# Fri3D_2024_ESP32.net
KiCad netlist of a schematic drawn in Altium Designer
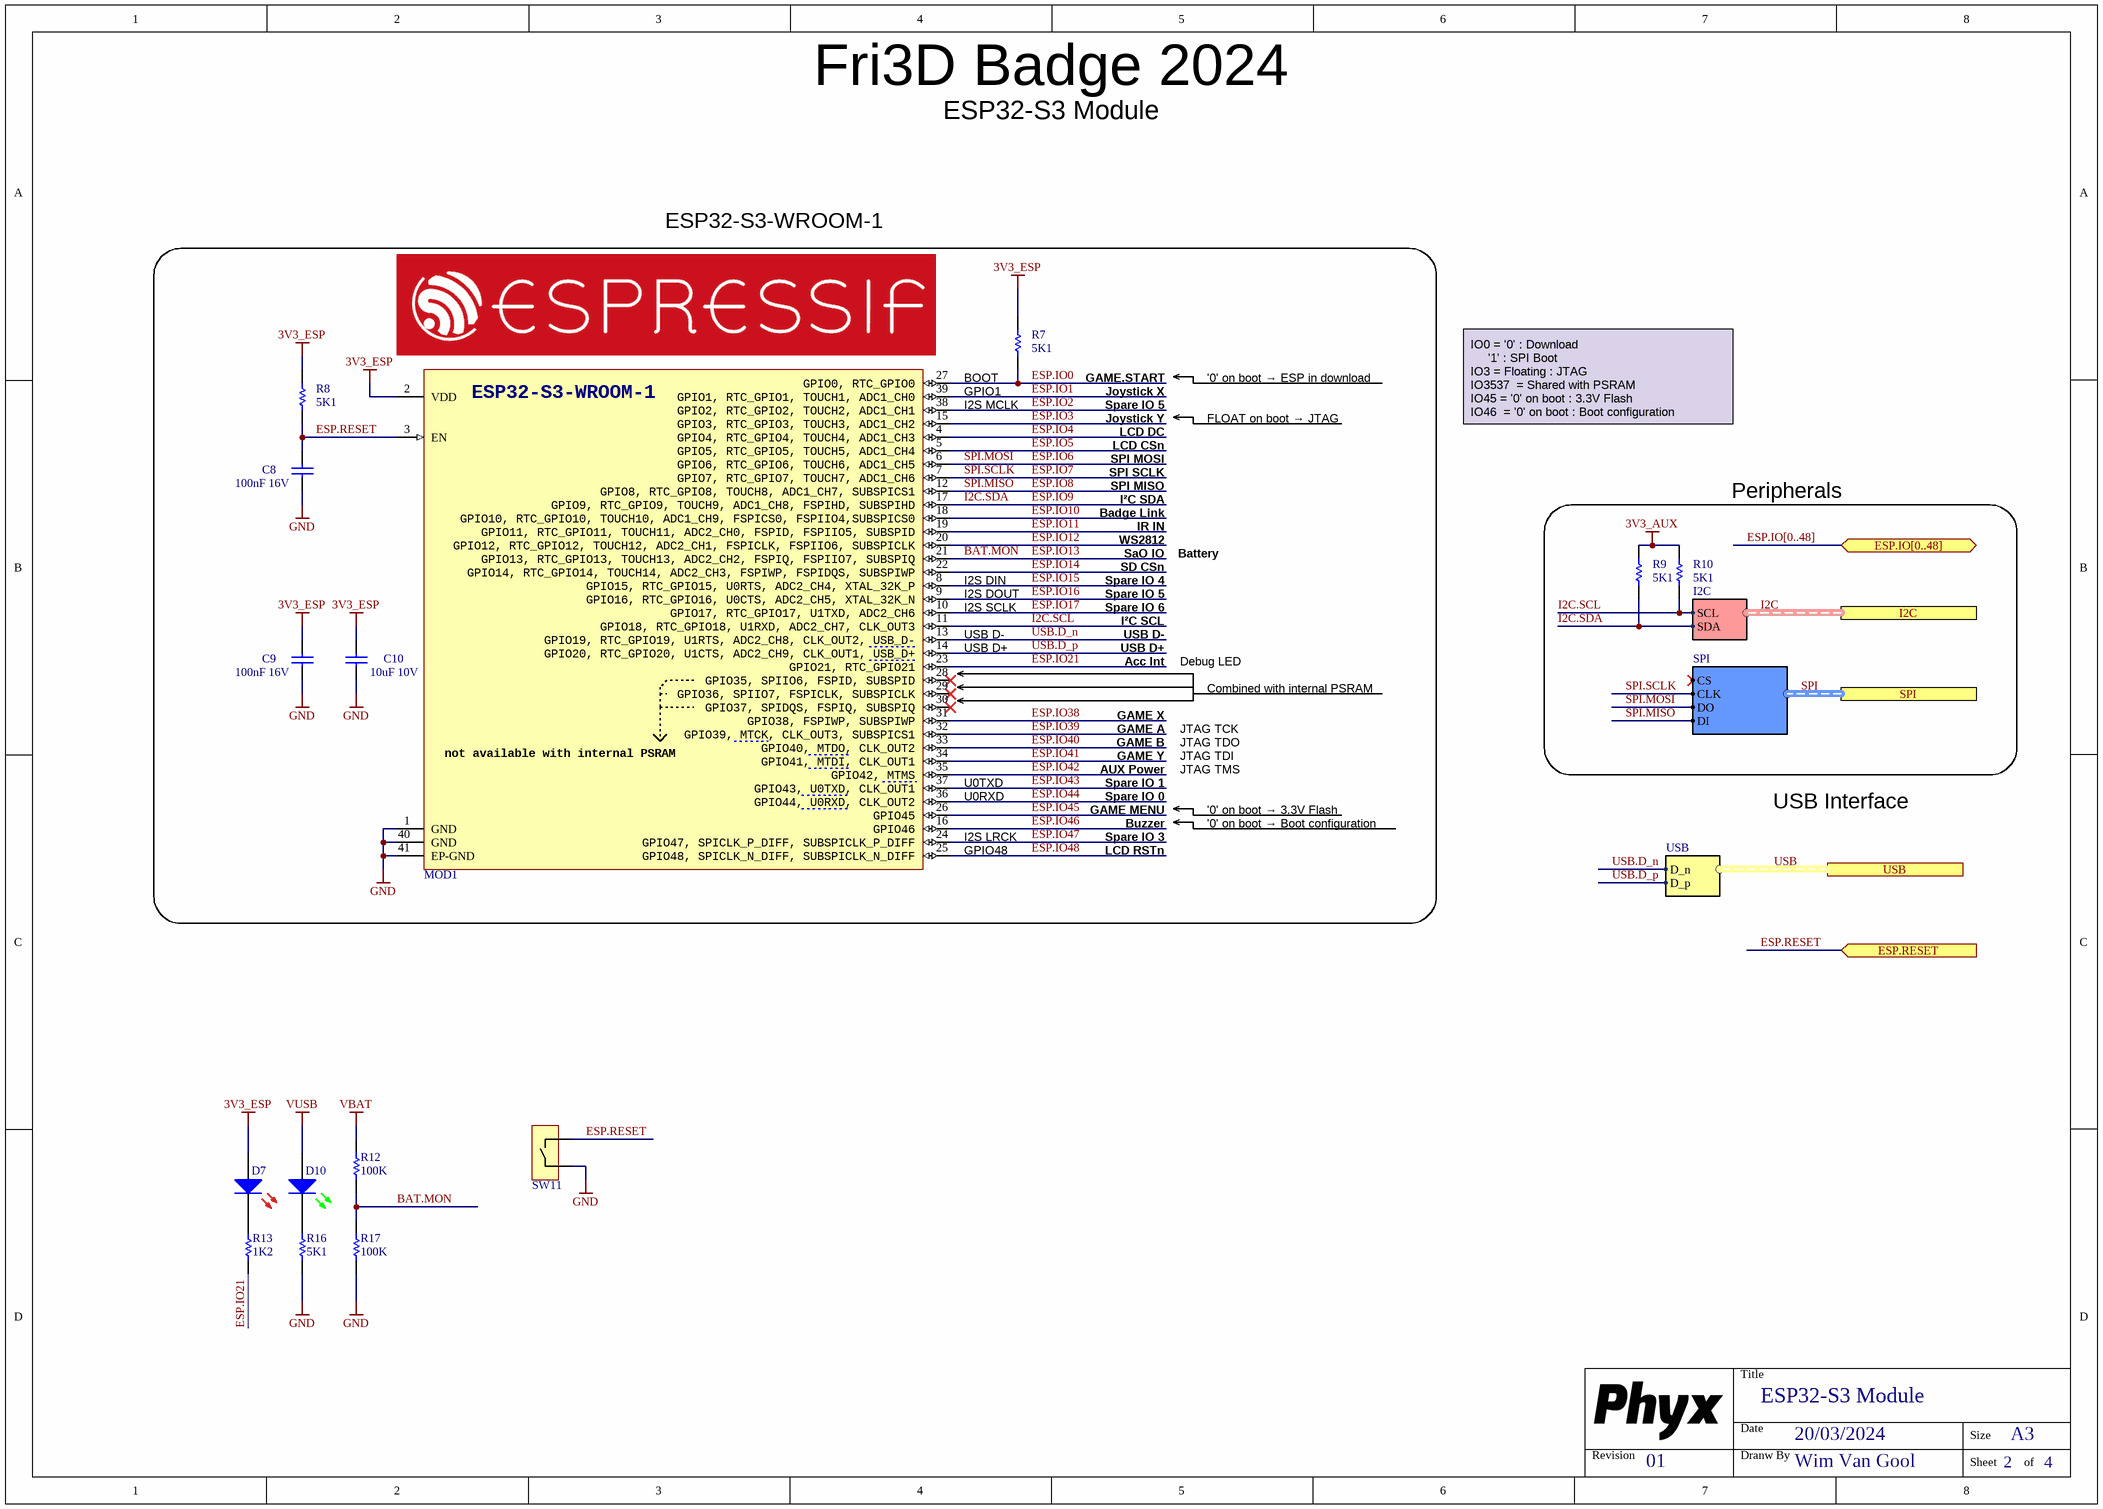
[diagram p0: Fri3D_2024_ESP32.SchDoc]

(export (version "E")
  (design (tool "Eeschema 10.0.6"))
  (components
    (comp (ref "C8")
      (value "100nF 16V")
      (footprint "C0603_N")
      (description "Capacitor Ceramic")
      (libsource (lib "Phyx_Components") (part "CAP_CERAMIC"))
    )
    (comp (ref "C9")
      (value "100nF 16V")
      (footprint "C0603_N")
      (description "Capacitor Ceramic")
      (libsource (lib "Phyx_Components") (part "CAP_CERAMIC"))
    )
    (comp (ref "C10")
      (value "10uF 10V")
      (footprint "C0805_N")
      (description "Capacitor Ceramic")
      (fields (field (name "Comment") "CAP_CERAMIC"))
      (libsource (lib "Phyx_Components") (part "CAP_CERAMIC"))
    )
    (comp (ref "D7")
      (value "Default 0805 Red LED")
      (footprint "LED_0805_RD")
      (description "=Description")
      (libsource (lib "Phyx_Components") (part "LED_RED"))
    )
    (comp (ref "D10")
      (value "Default 0805 Green LED")
      (footprint "LED_0805_GR")
      (description "=Description")
      (libsource (lib "Phyx_Components") (part "LED_GREEN"))
    )
    (comp (ref "MOD1")
      (value "ESP32-S3 based WROOM-1 16MB Flash, 8MB PSRAM")
      (footprint "ESP-ESP32-S3-WROOM-1")
      (description "WiFi # MOD ESP32-S3-WROOM-1")
      (libsource (lib "Phyx_Components") (part "ESP-ESP32-S3-WROOM-1"))
    )
    (comp (ref "R7")
      (value "5K1")
      (footprint "R0603_N")
      (fields (field (name "Comment") "RESISTOR"))
      (libsource (lib "Phyx_Components") (part "RESISTOR"))
    )
    (comp (ref "R8")
      (value "5K1")
      (footprint "R0603_N")
      (fields (field (name "Comment") "RESISTOR"))
      (libsource (lib "Phyx_Components") (part "RESISTOR"))
    )
    (comp (ref "R9")
      (value "5K1")
      (footprint "R0603_N")
      (fields (field (name "Comment") "RESISTOR"))
      (libsource (lib "Phyx_Components") (part "RESISTOR"))
    )
    (comp (ref "R10")
      (value "5K1")
      (footprint "R0603_N")
      (fields (field (name "Comment") "RESISTOR"))
      (libsource (lib "Phyx_Components") (part "RESISTOR"))
    )
    (comp (ref "R12")
      (value "100K")
      (footprint "R0603_N")
      (fields (field (name "Comment") "RESISTOR"))
      (libsource (lib "Phyx_Components") (part "RESISTOR"))
    )
    (comp (ref "R13")
      (value "1K2")
      (footprint "R0603_N")
      (fields (field (name "Comment") "RESISTOR"))
      (libsource (lib "Phyx_Components") (part "RESISTOR"))
    )
    (comp (ref "R16")
      (value "5K1")
      (footprint "R0603_N")
      (fields (field (name "Comment") "RESISTOR"))
      (libsource (lib "Phyx_Components") (part "RESISTOR"))
    )
    (comp (ref "R17")
      (value "100K")
      (footprint "R0603_N")
      (fields (field (name "Comment") "RESISTOR"))
      (libsource (lib "Phyx_Components") (part "RESISTOR"))
    )
    (comp (ref "SW11")
      (value "SKPMAME010 6x6 TACTG Switch")
      (footprint "ALPS_SKPMAME010")
      (libsource (lib "Phyx_Components") (part "SW_TACT"))
    )
  )
  (nets
    (net (code "23") (name "/ESP.IO0") (class "Default")
      (node (ref "MOD1") (pin "27") (pinfunction "GPIO0,_RTC_GPIO0_27") (pintype "bidirectional"))
      (node (ref "R7") (pin "2") (pinfunction "2_2") (pintype "passive"))
    )
    (net (code "24") (name "/ESP.IO1") (class "Default")
      (node (ref "MOD1") (pin "39") (pinfunction "GPIO1,_RTC_GPIO1,_TOUCH1,_ADC1_CH0_39") (pintype "bidirectional"))
    )
    (net (code "25") (name "/ESP.IO2") (class "Default")
      (node (ref "MOD1") (pin "38") (pinfunction "GPIO2,_RTC_GPIO2,_TOUCH2,_ADC1_CH1_38") (pintype "bidirectional"))
    )
    (net (code "26") (name "/ESP.IO3") (class "Default")
      (node (ref "MOD1") (pin "15") (pinfunction "GPIO3,_RTC_GPIO3,_TOUCH3,_ADC1_CH2_15") (pintype "bidirectional"))
    )
    (net (code "27") (name "/ESP.IO4") (class "Default")
      (node (ref "MOD1") (pin "4") (pinfunction "GPIO4,_RTC_GPIO4,_TOUCH4,_ADC1_CH3_4") (pintype "bidirectional"))
    )
    (net (code "28") (name "/ESP.IO5") (class "Default")
      (node (ref "MOD1") (pin "5") (pinfunction "GPIO5,_RTC_GPIO5,_TOUCH5,_ADC1_CH4_5") (pintype "bidirectional"))
    )
    (net (code "29") (name "/ESP.IO6") (class "Default")
      (node (ref "MOD1") (pin "6") (pinfunction "GPIO6,_RTC_GPIO6,_TOUCH6,_ADC1_CH5_6") (pintype "bidirectional"))
    )
    (net (code "30") (name "/ESP.IO7") (class "Default")
      (node (ref "MOD1") (pin "7") (pinfunction "GPIO7,_RTC_GPIO7,_TOUCH7,_ADC1_CH6_7") (pintype "bidirectional"))
    )
    (net (code "31") (name "/ESP.IO8") (class "Default")
      (node (ref "MOD1") (pin "12") (pinfunction "GPIO8,_RTC_GPIO8,_TOUCH8,_ADC1_CH7,_SUBSPICS1_12") (pintype "bidirectional"))
    )
    (net (code "32") (name "/ESP.IO9") (class "Default")
      (node (ref "MOD1") (pin "17") (pinfunction "GPIO9,_RTC_GPIO9,_TOUCH9,_ADC1_CH8,_FSPIHD,_SUBSPIHD_17") (pintype "bidirectional"))
      (node (ref "R9") (pin "2") (pinfunction "2_2") (pintype "passive"))
    )
    (net (code "33") (name "/ESP.IO10") (class "Default")
      (node (ref "MOD1") (pin "18") (pinfunction "GPIO10,_RTC_GPIO10,_TOUCH10,_ADC1_CH9,_FSPICS0,_FSPIIO4,SUBSPICS0_18") (pintype "bidirectional"))
    )
    (net (code "34") (name "/ESP.IO11") (class "Default")
      (node (ref "MOD1") (pin "19") (pinfunction "GPIO11,_RTC_GPIO11,_TOUCH11,_ADC2_CH0,_FSPID,_FSPIIO5,_SUBSPID_19") (pintype "bidirectional"))
    )
    (net (code "35") (name "/ESP.IO12") (class "Default")
      (node (ref "MOD1") (pin "20") (pinfunction "GPIO12,_RTC_GPIO12,_TOUCH12,_ADC2_CH1,_FSPICLK,_FSPIIO6,_SUBSPICLK_20") (pintype "bidirectional"))
    )
    (net (code "36") (name "/ESP.IO13") (class "Default")
      (node (ref "MOD1") (pin "21") (pinfunction "GPIO13,_RTC_GPIO13,_TOUCH13,_ADC2_CH2,_FSPIQ,_FSPIIO7,_SUBSPIQ_21") (pintype "bidirectional"))
      (node (ref "R12") (pin "2") (pinfunction "2_2") (pintype "passive"))
      (node (ref "R17") (pin "1") (pinfunction "1_1") (pintype "passive"))
    )
    (net (code "37") (name "/ESP.IO14") (class "Default")
      (node (ref "MOD1") (pin "22") (pinfunction "GPIO14,_RTC_GPIO14,_TOUCH14,_ADC2_CH3,_FSPIWP,_FSPIDQS,_SUBSPIWP_22") (pintype "bidirectional"))
    )
    (net (code "38") (name "/ESP.IO15") (class "Default")
      (node (ref "MOD1") (pin "8") (pinfunction "GPIO15,_RTC_GPIO15,_U0RTS,_ADC2_CH4,_XTAL_32K_P_8") (pintype "bidirectional"))
    )
    (net (code "39") (name "/ESP.IO16") (class "Default")
      (node (ref "MOD1") (pin "9") (pinfunction "GPIO16,_RTC_GPIO16,_U0CTS,_ADC2_CH5,_XTAL_32K_N_9") (pintype "bidirectional"))
    )
    (net (code "40") (name "/ESP.IO17") (class "Default")
      (node (ref "MOD1") (pin "10") (pinfunction "GPIO17,_RTC_GPIO17,_U1TXD,_ADC2_CH6_10") (pintype "bidirectional"))
    )
    (net (code "41") (name "/ESP.IO21") (class "Default")
      (node (ref "MOD1") (pin "23") (pinfunction "GPIO21,_RTC_GPIO21_23") (pintype "bidirectional"))
      (node (ref "R13") (pin "2") (pinfunction "2_2") (pintype "passive"))
    )
    (net (code "42") (name "/ESP.IO38") (class "Default")
      (node (ref "MOD1") (pin "31") (pinfunction "GPIO38,_FSPIWP,_SUBSPIWP_31") (pintype "bidirectional"))
    )
    (net (code "43") (name "/ESP.IO39") (class "Default")
      (node (ref "MOD1") (pin "32") (pinfunction "GPIO39,_MTCK,_CLK_OUT3,_SUBSPICS1_32") (pintype "bidirectional"))
    )
    (net (code "44") (name "/ESP.IO40") (class "Default")
      (node (ref "MOD1") (pin "33") (pinfunction "GPIO40,_MTDO,_CLK_OUT2_33") (pintype "bidirectional"))
    )
    (net (code "45") (name "/ESP.IO41") (class "Default")
      (node (ref "MOD1") (pin "34") (pinfunction "GPIO41,_MTDI,_CLK_OUT1_34") (pintype "bidirectional"))
    )
    (net (code "46") (name "/ESP.IO42") (class "Default")
      (node (ref "MOD1") (pin "35") (pinfunction "GPIO42,_MTMS_35") (pintype "bidirectional"))
    )
    (net (code "47") (name "/ESP.IO43") (class "Default")
      (node (ref "MOD1") (pin "37") (pinfunction "GPIO43,_U0TXD,_CLK_OUT1_37") (pintype "bidirectional"))
    )
    (net (code "48") (name "/ESP.IO44") (class "Default")
      (node (ref "MOD1") (pin "36") (pinfunction "GPIO44,_U0RXD,_CLK_OUT2_36") (pintype "bidirectional"))
    )
    (net (code "49") (name "/ESP.IO45") (class "Default")
      (node (ref "MOD1") (pin "26") (pinfunction "GPIO45_26") (pintype "bidirectional"))
    )
    (net (code "50") (name "/ESP.IO46") (class "Default")
      (node (ref "MOD1") (pin "16") (pinfunction "GPIO46_16") (pintype "bidirectional"))
    )
    (net (code "51") (name "/ESP.IO47") (class "Default")
      (node (ref "MOD1") (pin "24") (pinfunction "GPIO47,_SPICLK_P_DIFF,_SUBSPICLK_P_DIFF_24") (pintype "bidirectional"))
    )
    (net (code "52") (name "/ESP.IO48") (class "Default")
      (node (ref "MOD1") (pin "25") (pinfunction "GPIO48,_SPICLK_N_DIFF,_SUBSPICLK_N_DIFF_25") (pintype "bidirectional"))
    )
    (net (code "54") (name "/ESP.RESET") (class "Default")
      (node (ref "C8") (pin "1") (pinfunction "1_1") (pintype "passive"))
      (node (ref "MOD1") (pin "3") (pinfunction "EN_3") (pintype "input"))
      (node (ref "R8") (pin "2") (pinfunction "2_2") (pintype "passive"))
      (node (ref "SW11") (pin "1") (pinfunction "1_1") (pintype "passive"))
    )
    (net (code "55") (name "/I2C.SCL") (class "Default")
      (node (ref "MOD1") (pin "11") (pinfunction "GPIO18,_RTC_GPIO18,_U1RXD,_ADC2_CH7,_CLK_OUT3_11") (pintype "bidirectional"))
      (node (ref "R10") (pin "2") (pinfunction "2_2") (pintype "passive"))
    )
    (net (code "58") (name "/USB.D_n") (class "Default")
      (node (ref "MOD1") (pin "13") (pinfunction "GPIO19,_RTC_GPIO19,_U1RTS,_ADC2_CH8,_CLK_OUT2,_USB_D-_13") (pintype "bidirectional"))
    )
    (net (code "59") (name "/USB.D_p") (class "Default")
      (node (ref "MOD1") (pin "14") (pinfunction "GPIO20,_RTC_GPIO20,_U1CTS,_ADC2_CH9,_CLK_OUT1,_USB_D+_14") (pintype "bidirectional"))
    )
    (net (code "61") (name "3V3_AUX") (class "Default")
      (node (ref "R10") (pin "1") (pinfunction "1_1") (pintype "passive"))
      (node (ref "R9") (pin "1") (pinfunction "1_1") (pintype "passive"))
    )
    (net (code "62") (name "3V3_ESP") (class "Default")
      (node (ref "C10") (pin "1") (pinfunction "1_1") (pintype "passive"))
      (node (ref "C9") (pin "1") (pinfunction "1_1") (pintype "passive"))
      (node (ref "D7") (pin "1") (pinfunction "A_1") (pintype "passive"))
      (node (ref "MOD1") (pin "2") (pinfunction "VDD_2") (pintype "power_in"))
      (node (ref "R7") (pin "1") (pinfunction "1_1") (pintype "passive"))
      (node (ref "R8") (pin "1") (pinfunction "1_1") (pintype "passive"))
    )
    (net (code "63") (name "GND") (class "Default")
      (node (ref "C10") (pin "2") (pinfunction "2_2") (pintype "passive"))
      (node (ref "C8") (pin "2") (pinfunction "2_2") (pintype "passive"))
      (node (ref "C9") (pin "2") (pinfunction "2_2") (pintype "passive"))
      (node (ref "MOD1") (pin "1") (pinfunction "GND_1") (pintype "power_in"))
      (node (ref "MOD1") (pin "40") (pinfunction "GND_40") (pintype "power_in"))
      (node (ref "MOD1") (pin "41") (pinfunction "EP-GND_41") (pintype "power_in"))
      (node (ref "R16") (pin "2") (pinfunction "2_2") (pintype "passive"))
      (node (ref "R17") (pin "2") (pinfunction "2_2") (pintype "passive"))
      (node (ref "SW11") (pin "2") (pinfunction "2_2") (pintype "passive"))
    )
    (net (code "64") (name "Net-(D7-K)") (class "Default")
      (node (ref "D7") (pin "2") (pinfunction "K_2") (pintype "passive"))
      (node (ref "R13") (pin "1") (pinfunction "1_1") (pintype "passive"))
    )
    (net (code "65") (name "Net-(D10-K)") (class "Default")
      (node (ref "D10") (pin "2") (pinfunction "K_2") (pintype "passive"))
      (node (ref "R16") (pin "1") (pinfunction "1_1") (pintype "passive"))
    )
    (net (code "66") (name "VBAT") (class "Default")
      (node (ref "R12") (pin "1") (pinfunction "1_1") (pintype "passive"))
    )
    (net (code "67") (name "VUSB") (class "Default")
      (node (ref "D10") (pin "1") (pinfunction "A_1") (pintype "passive"))
    )
    (net (code "68") (name "unconnected-(MOD1-GPIO35,_SPIIO6,_FSPID,_SUBSPID-Pad28)") (class "Default")
      (node (ref "MOD1") (pin "28") (pinfunction "GPIO35,_SPIIO6,_FSPID,_SUBSPID_28") (pintype "bidirectional+no_connect"))
    )
    (net (code "69") (name "unconnected-(MOD1-GPIO36,_SPIIO7,_FSPICLK,_SUBSPICLK-Pad29)") (class "Default")
      (node (ref "MOD1") (pin "29") (pinfunction "GPIO36,_SPIIO7,_FSPICLK,_SUBSPICLK_29") (pintype "bidirectional+no_connect"))
    )
    (net (code "70") (name "unconnected-(MOD1-GPIO37,_SPIDQS,_FSPIQ,_SUBSPIQ-Pad30)") (class "Default")
      (node (ref "MOD1") (pin "30") (pinfunction "GPIO37,_SPIDQS,_FSPIQ,_SUBSPIQ_30") (pintype "bidirectional+no_connect"))
    )
  )
)
